# ChargeBoost.net
KiCad netlist of a schematic drawn in EAGLE
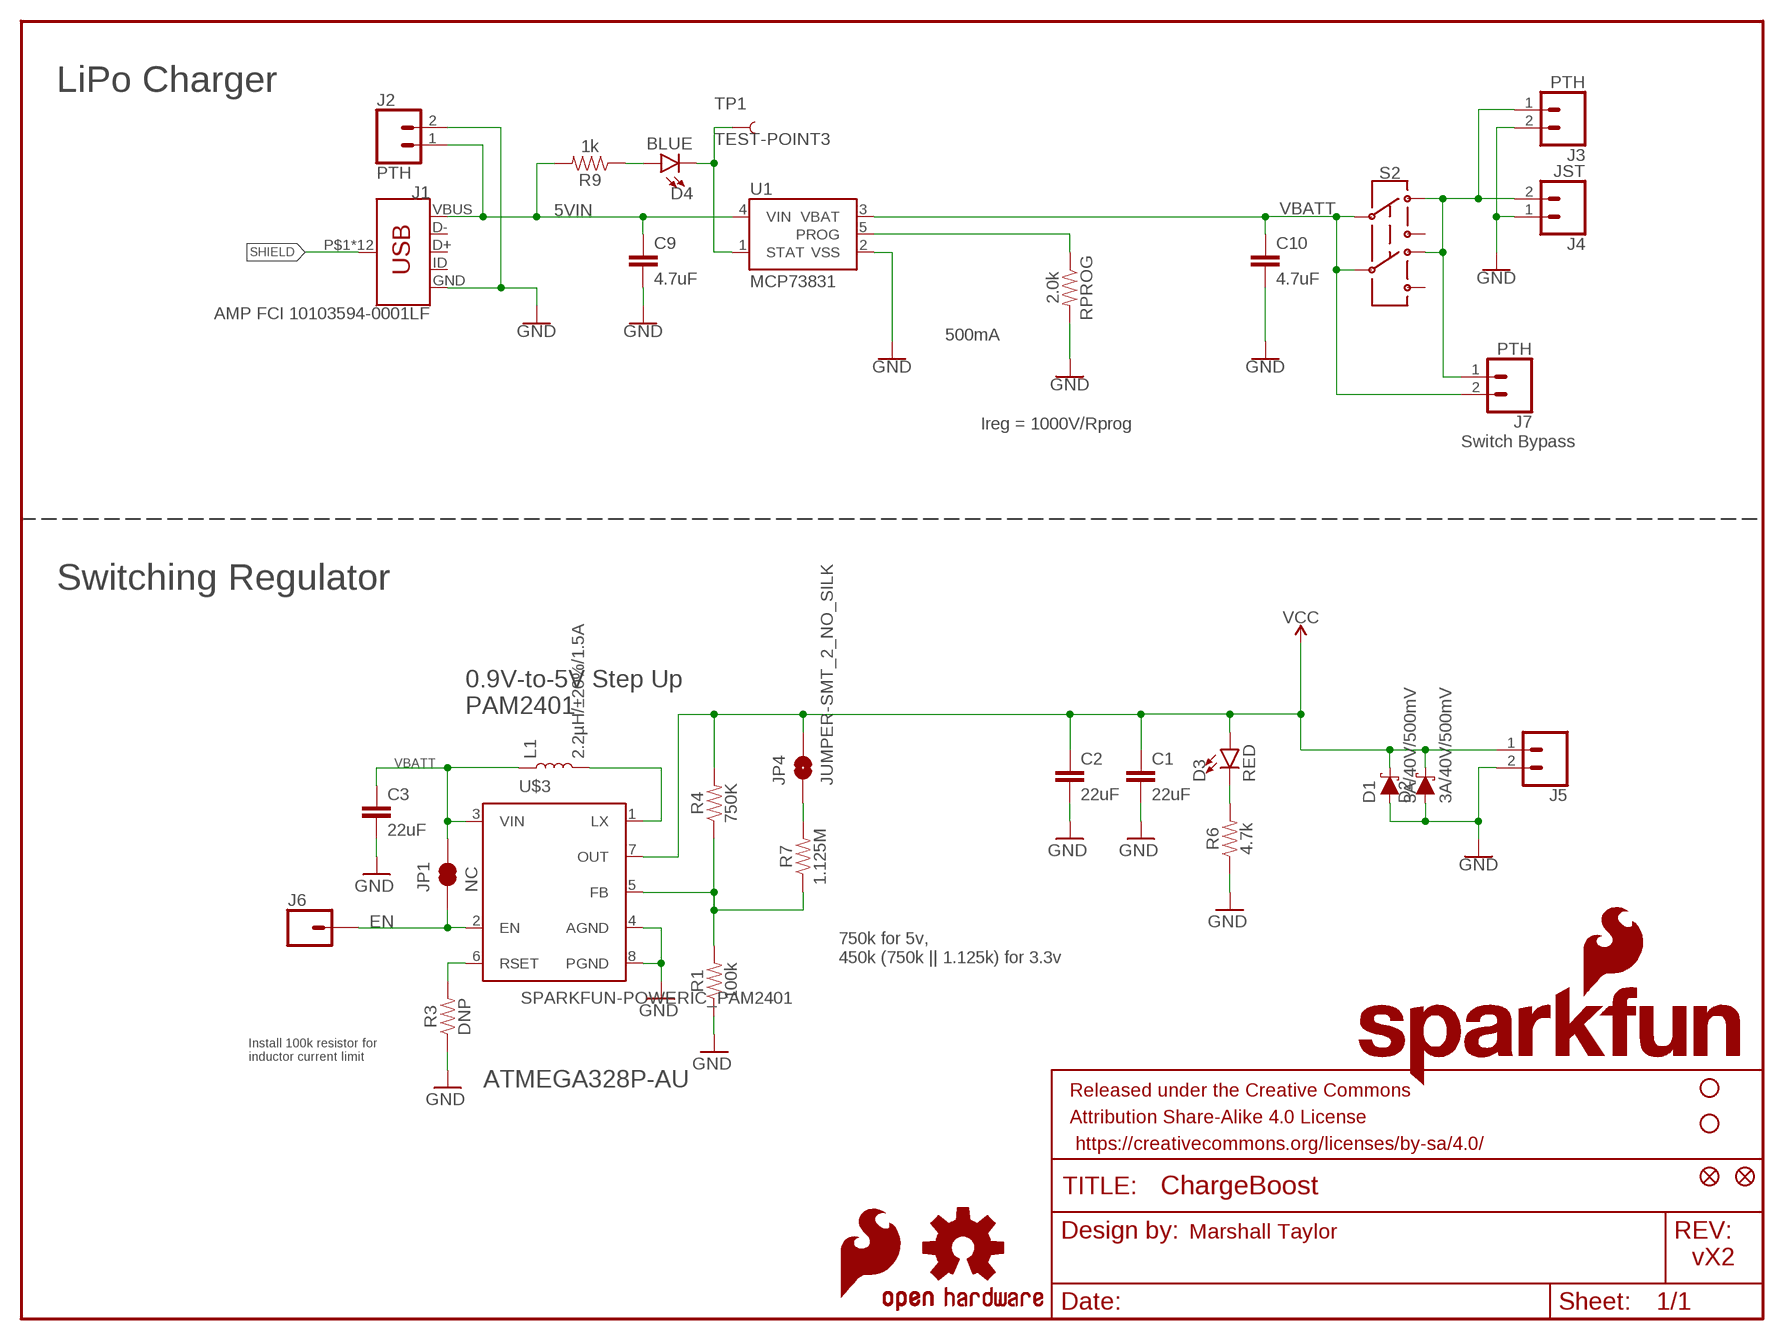
[diagram p0: schematic, sheet 1]

(export (version "E")
  (design (tool "Eeschema 10.0.6"))
  (components
    (comp (ref "C1")
      (value "22uF")
      (footprint "eagle-import:0805")
      (libsource (lib "eagle-import") (part "22UF-0805-6.3V-20%"))
    )
    (comp (ref "C2")
      (value "22uF")
      (footprint "eagle-import:0805")
      (libsource (lib "eagle-import") (part "22UF-0805-6.3V-20%"))
    )
    (comp (ref "C3")
      (value "22uF")
      (footprint "eagle-import:0805")
      (libsource (lib "eagle-import") (part "22UF-0805-6.3V-20%"))
    )
    (comp (ref "C9")
      (value "4.7uF")
      (footprint "eagle-import:0603")
      (libsource (lib "eagle-import") (part "4.7UF0603"))
    )
    (comp (ref "C10")
      (value "4.7uF")
      (footprint "eagle-import:0603")
      (libsource (lib "eagle-import") (part "4.7UF0603"))
    )
    (comp (ref "D1")
      (value "3A/40V/500mV")
      (footprint "eagle-import:SMA-DIODE")
      (libsource (lib "eagle-import") (part "DIODE-SCHOTTKY-B340A"))
    )
    (comp (ref "D2")
      (value "3A/40V/500mV")
      (footprint "eagle-import:SMA-DIODE")
      (libsource (lib "eagle-import") (part "DIODE-SCHOTTKY-B340A"))
    )
    (comp (ref "D3")
      (value "RED")
      (footprint "eagle-import:LED-0603")
      (libsource (lib "eagle-import") (part "LED-RED0603"))
    )
    (comp (ref "D4")
      (value "BLUE")
      (footprint "eagle-import:LED-0603")
      (libsource (lib "eagle-import") (part "LED-BLUE0603"))
    )
    (comp (ref "FRAME1")
      (value "FRAME-LETTER")
      (footprint "eagle-import:CREATIVE_COMMONS")
      (libsource (lib "eagle-import") (part "FRAME-LETTER"))
    )
    (comp (ref "J1")
      (value "AMP FCI 10103594-0001LF")
      (footprint "eagle-import:USB-MICROB-PTH")
      (libsource (lib "eagle-import") (part "USB_MICRO-B_HALF_PTH"))
    )
    (comp (ref "J2")
      (value "PTH")
      (footprint "eagle-import:1X02")
      (libsource (lib "eagle-import") (part "CONN_02"))
    )
    (comp (ref "J3")
      (value "PTH")
      (footprint "eagle-import:1X02")
      (libsource (lib "eagle-import") (part "CONN_02"))
    )
    (comp (ref "J4")
      (value "JST")
      (footprint "eagle-import:JST-2-SMD")
      (libsource (lib "eagle-import") (part "CONN_02-JST-2MM-SMT"))
    )
    (comp (ref "J5")
      (value "CONN_02")
      (footprint "eagle-import:1X02")
      (libsource (lib "eagle-import") (part "CONN_02"))
    )
    (comp (ref "J6")
      (value "CONN_01")
      (footprint "eagle-import:1X01")
      (libsource (lib "eagle-import") (part "CONN_01"))
    )
    (comp (ref "J7")
      (value "PTH")
      (footprint "eagle-import:1X02")
      (libsource (lib "eagle-import") (part "CONN_02"))
    )
    (comp (ref "JP1")
      (value "NC")
      (footprint "eagle-import:SMT-JUMPER_2_NC_TRACE_NO-SILK")
      (libsource (lib "eagle-import") (part "JUMPER-SMT_2_NC_TRACE_NO-SILK"))
    )
    (comp (ref "JP2")
      (value "FIDUCIAL1X2")
      (footprint "eagle-import:FIDUCIAL-1X2")
      (libsource (lib "eagle-import") (part "FIDUCIAL1X2"))
    )
    (comp (ref "JP3")
      (value "SFE_LOGO_NAME_FLAME.1_INCH")
      (footprint "eagle-import:SFE_LOGO_NAME_FLAME_.1")
      (libsource (lib "eagle-import") (part "SFE_LOGO_NAME_FLAME.1_INCH"))
    )
    (comp (ref "JP4")
      (value "JUMPER-SMT_2_NO_SILK")
      (footprint "eagle-import:SMT-JUMPER_2_NO_SILK")
      (libsource (lib "eagle-import") (part "JUMPER-SMT_2_NO_SILK"))
    )
    (comp (ref "JP6")
      (value "STAND-OFF")
      (footprint "eagle-import:STAND-OFF")
      (libsource (lib "eagle-import") (part "STAND-OFF"))
    )
    (comp (ref "JP7")
      (value "STAND-OFF")
      (footprint "eagle-import:STAND-OFF")
      (libsource (lib "eagle-import") (part "STAND-OFF"))
    )
    (comp (ref "JP16")
      (value "FIDUCIAL1X2")
      (footprint "eagle-import:FIDUCIAL-1X2")
      (libsource (lib "eagle-import") (part "FIDUCIAL1X2"))
    )
    (comp (ref "L1")
      (value "2.2µH/±20%/1.5A")
      (footprint "eagle-import:INDUCTOR_2.2UHCOPY")
      (libsource (lib "eagle-import") (part "INDUCTORCOPY-VLF4012AT-2.2UH"))
    )
    (comp (ref "LOGO1")
      (value "SFE_LOGO_FLAME.1_INCH")
      (footprint "eagle-import:SFE_LOGO_FLAME_.1")
      (libsource (lib "eagle-import") (part "SFE_LOGO_FLAME.1_INCH"))
    )
    (comp (ref "R1")
      (value "100k")
      (footprint "eagle-import:0603")
      (libsource (lib "eagle-import") (part "100KOHM-0603-1/10W-1%"))
    )
    (comp (ref "R3")
      (value "DNP")
      (footprint "eagle-import:0603")
      (libsource (lib "eagle-import") (part "100KOHM-0603-1/10W-1%"))
    )
    (comp (ref "R4")
      (value "750K")
      (footprint "eagle-import:0603")
      (libsource (lib "eagle-import") (part "750OHM-0603-1/10W-1%"))
    )
    (comp (ref "R6")
      (value "4.7k")
      (footprint "eagle-import:0603")
      (libsource (lib "eagle-import") (part "4.7KOHM-0603-1/10W-1%"))
    )
    (comp (ref "R7")
      (value "1.125M")
      (footprint "eagle-import:0603")
      (libsource (lib "eagle-import") (part "750OHM-0603-1/10W-1%"))
    )
    (comp (ref "R9")
      (value "1k")
      (footprint "eagle-import:0603")
      (libsource (lib "eagle-import") (part "1KOHM-0603-1/10W-1%"))
    )
    (comp (ref "RPROG")
      (value "2.0k")
      (footprint "eagle-import:0603")
      (libsource (lib "eagle-import") (part "2.0KOHM-0603-1/10W-5%"))
    )
    (comp (ref "S2")
      (value "SWITCH-DPDT-SMD-AYZ0202")
      (footprint "eagle-import:SWITCH_DPDT_SMD_AYZ0202")
      (libsource (lib "eagle-import") (part "SWITCH-DPDT-SMD-AYZ0202"))
    )
    (comp (ref "TP1")
      (value "TEST-POINT3")
      (footprint "eagle-import:PAD.03X.03")
      (libsource (lib "eagle-import") (part "TEST-POINT3"))
    )
    (comp (ref "U$1")
      (value "OSHW-LOGOS")
      (footprint "eagle-import:OSHW-LOGO-S")
      (libsource (lib "eagle-import") (part "OSHW-LOGOS"))
    )
    (comp (ref "U$3")
      (value "SPARKFUN-POWERIC_PAM2401")
      (footprint "eagle-import:SPARKFUN-POWERIC_MSOP8")
      (libsource (lib "eagle-import") (part "SPARKFUN-POWERIC_PAM2401"))
    )
    (comp (ref "U1")
      (value "MCP73831")
      (footprint "eagle-import:SOT23-5")
      (libsource (lib "eagle-import") (part "MCP73831"))
    )
  )
  (nets
    (net (code "1") (name "/5VIN") (class "Default")
      (node (ref "C9") (pin "1") (pinfunction "1_1") (pintype "passive"))
      (node (ref "J1") (pin "VBUS") (pinfunction "VBUS_VBUS") (pintype "power_in"))
      (node (ref "J2") (pin "1") (pinfunction "1_1") (pintype "passive"))
      (node (ref "R9") (pin "2") (pinfunction "2_2") (pintype "passive"))
      (node (ref "U1") (pin "4") (pinfunction "VIN_4") (pintype "power_in"))
    )
    (net (code "2") (name "/EN") (class "Default")
      (node (ref "J6") (pin "1") (pinfunction "1_1") (pintype "passive"))
      (node (ref "JP1") (pin "1") (pinfunction "1_1") (pintype "passive"))
      (node (ref "U$3") (pin "2") (pinfunction "EN_2") (pintype "bidirectional"))
    )
    (net (code "3") (name "/VBATT") (class "Default")
      (node (ref "C10") (pin "1") (pinfunction "1_1") (pintype "passive"))
      (node (ref "C3") (pin "1") (pinfunction "1_1") (pintype "passive"))
      (node (ref "J7") (pin "2") (pinfunction "2_2") (pintype "passive"))
      (node (ref "JP1") (pin "2") (pinfunction "2_2") (pintype "passive"))
      (node (ref "L1") (pin "P$1") (pinfunction "1_P$1") (pintype "passive"))
      (node (ref "S2") (pin "2") (pinfunction "2_2") (pintype "bidirectional"))
      (node (ref "S2") (pin "5") (pinfunction "5_5") (pintype "bidirectional"))
      (node (ref "U$3") (pin "3") (pinfunction "VIN_3") (pintype "bidirectional"))
      (node (ref "U1") (pin "3") (pinfunction "VBAT_3") (pintype "power_in"))
    )
    (net (code "4") (name "GND") (class "Default")
      (node (ref "C1") (pin "2") (pinfunction "2_2") (pintype "passive"))
      (node (ref "C10") (pin "2") (pinfunction "2_2") (pintype "passive"))
      (node (ref "C2") (pin "2") (pinfunction "2_2") (pintype "passive"))
      (node (ref "C3") (pin "2") (pinfunction "2_2") (pintype "passive"))
      (node (ref "C9") (pin "2") (pinfunction "2_2") (pintype "passive"))
      (node (ref "D1") (pin "A") (pinfunction "A_A") (pintype "passive"))
      (node (ref "D2") (pin "A") (pinfunction "A_A") (pintype "passive"))
      (node (ref "J1") (pin "GND") (pinfunction "GND_GND") (pintype "power_in"))
      (node (ref "J2") (pin "2") (pinfunction "2_2") (pintype "passive"))
      (node (ref "J3") (pin "2") (pinfunction "2_2") (pintype "passive"))
      (node (ref "J4") (pin "1") (pinfunction "2_1") (pintype "passive"))
      (node (ref "J5") (pin "2") (pinfunction "2_2") (pintype "passive"))
      (node (ref "R1") (pin "1") (pinfunction "1_1") (pintype "passive"))
      (node (ref "R3") (pin "1") (pinfunction "1_1") (pintype "passive"))
      (node (ref "R6") (pin "1") (pinfunction "1_1") (pintype "passive"))
      (node (ref "RPROG") (pin "2") (pinfunction "2_2") (pintype "passive"))
      (node (ref "U$3") (pin "4") (pinfunction "AGND_4") (pintype "bidirectional"))
      (node (ref "U$3") (pin "8") (pinfunction "PGND_8") (pintype "bidirectional"))
      (node (ref "U1") (pin "2") (pinfunction "VSS_2") (pintype "power_in"))
    )
    (net (code "5") (name "Net-(D3-PadC)") (class "Default")
      (node (ref "D3") (pin "C") (pinfunction "C_C") (pintype "passive"))
      (node (ref "R6") (pin "2") (pinfunction "2_2") (pintype "passive"))
    )
    (net (code "6") (name "Net-(D4-PadA)") (class "Default")
      (node (ref "D4") (pin "A") (pinfunction "A_A") (pintype "passive"))
      (node (ref "R9") (pin "1") (pinfunction "1_1") (pintype "passive"))
    )
    (net (code "7") (name "Net-(J4-1)") (class "Default")
      (node (ref "J3") (pin "1") (pinfunction "1_1") (pintype "passive"))
      (node (ref "J4") (pin "2") (pinfunction "1_2") (pintype "passive"))
      (node (ref "J7") (pin "1") (pinfunction "1_1") (pintype "passive"))
      (node (ref "S2") (pin "1") (pinfunction "1_1") (pintype "bidirectional"))
      (node (ref "S2") (pin "4") (pinfunction "4_4") (pintype "bidirectional"))
    )
    (net (code "8") (name "Net-(JP4-Pad1)") (class "Default")
      (node (ref "JP4") (pin "1") (pinfunction "1_1") (pintype "passive"))
      (node (ref "R7") (pin "2") (pinfunction "2_2") (pintype "passive"))
    )
    (net (code "9") (name "Net-(L1-2)") (class "Default")
      (node (ref "L1") (pin "P$2") (pinfunction "2_P$2") (pintype "passive"))
      (node (ref "U$3") (pin "1") (pinfunction "LX_1") (pintype "bidirectional"))
    )
    (net (code "10") (name "Net-(TP1-1)") (class "Default")
      (node (ref "D4") (pin "C") (pinfunction "C_C") (pintype "passive"))
      (node (ref "TP1") (pin "P$1") (pinfunction "1_P$1") (pintype "bidirectional"))
      (node (ref "U1") (pin "1") (pinfunction "STAT_1") (pintype "output"))
    )
    (net (code "11") (name "Net-(U$3-FB)") (class "Default")
      (node (ref "R1") (pin "2") (pinfunction "2_2") (pintype "passive"))
      (node (ref "R4") (pin "1") (pinfunction "1_1") (pintype "passive"))
      (node (ref "R7") (pin "1") (pinfunction "1_1") (pintype "passive"))
      (node (ref "U$3") (pin "5") (pinfunction "FB_5") (pintype "bidirectional"))
    )
    (net (code "12") (name "Net-(U$3-RSET)") (class "Default")
      (node (ref "R3") (pin "2") (pinfunction "2_2") (pintype "passive"))
      (node (ref "U$3") (pin "6") (pinfunction "RSET_6") (pintype "bidirectional"))
    )
    (net (code "13") (name "Net-(U1-PROG)") (class "Default")
      (node (ref "RPROG") (pin "1") (pinfunction "1_1") (pintype "passive"))
      (node (ref "U1") (pin "5") (pinfunction "PROG_5") (pintype "input"))
    )
    (net (code "14") (name "SHIELD") (class "Default")
      (node (ref "J1") (pin "P$1") (pinfunction "SHIELD_P$1") (pintype "bidirectional"))
      (node (ref "J1") (pin "P$10") (pinfunction "SHIELD_P$10") (pintype "bidirectional"))
      (node (ref "J1") (pin "P$12") (pinfunction "SHIELD_P$12") (pintype "bidirectional"))
      (node (ref "J1") (pin "P$2") (pinfunction "SHIELD_P$2") (pintype "bidirectional"))
      (node (ref "J1") (pin "P$3") (pinfunction "SHIELD_P$3") (pintype "bidirectional"))
      (node (ref "J1") (pin "P$4") (pinfunction "SHIELD_P$4") (pintype "bidirectional"))
      (node (ref "J1") (pin "P$6") (pinfunction "SHIELD_P$6") (pintype "bidirectional"))
      (node (ref "J1") (pin "P$8") (pinfunction "SHIELD_P$8") (pintype "bidirectional"))
      (node (ref "J1") (pin "SHEILD2") (pinfunction "SHIELD_SHEILD2") (pintype "bidirectional"))
      (node (ref "J1") (pin "SHIELD") (pinfunction "SHIELD_SHIELD") (pintype "bidirectional"))
      (node (ref "J1") (pin "SHIELD3") (pinfunction "SHIELD_SHIELD3") (pintype "bidirectional"))
      (node (ref "J1") (pin "SHIELD4") (pinfunction "SHIELD_SHIELD4") (pintype "bidirectional"))
    )
    (net (code "15") (name "VCC") (class "Default")
      (node (ref "C1") (pin "1") (pinfunction "1_1") (pintype "passive"))
      (node (ref "C2") (pin "1") (pinfunction "1_1") (pintype "passive"))
      (node (ref "D1") (pin "C") (pinfunction "C_C") (pintype "passive"))
      (node (ref "D2") (pin "C") (pinfunction "C_C") (pintype "passive"))
      (node (ref "D3") (pin "A") (pinfunction "A_A") (pintype "passive"))
      (node (ref "J5") (pin "1") (pinfunction "1_1") (pintype "passive"))
      (node (ref "JP4") (pin "2") (pinfunction "2_2") (pintype "passive"))
      (node (ref "R4") (pin "2") (pinfunction "2_2") (pintype "passive"))
      (node (ref "U$3") (pin "7") (pinfunction "OUT_7") (pintype "bidirectional"))
    )
    (net (code "16") (name "unconnected-(J1-PadD+)") (class "Default")
      (node (ref "J1") (pin "D+") (pinfunction "D+_D+") (pintype "bidirectional"))
    )
    (net (code "17") (name "unconnected-(J1-PadD-)") (class "Default")
      (node (ref "J1") (pin "D-") (pinfunction "D-_D-") (pintype "bidirectional"))
    )
    (net (code "18") (name "unconnected-(J1-PadID)") (class "Default")
      (node (ref "J1") (pin "ID") (pinfunction "ID_ID") (pintype "bidirectional"))
    )
    (net (code "19") (name "unconnected-(S2-Pad3)") (class "Default")
      (node (ref "S2") (pin "3") (pinfunction "3_3") (pintype "bidirectional"))
    )
    (net (code "20") (name "unconnected-(S2-Pad6)") (class "Default")
      (node (ref "S2") (pin "6") (pinfunction "6_6") (pintype "bidirectional"))
    )
  )
)
